# CONN.net
KiCad netlist of a schematic drawn in Altium Designer
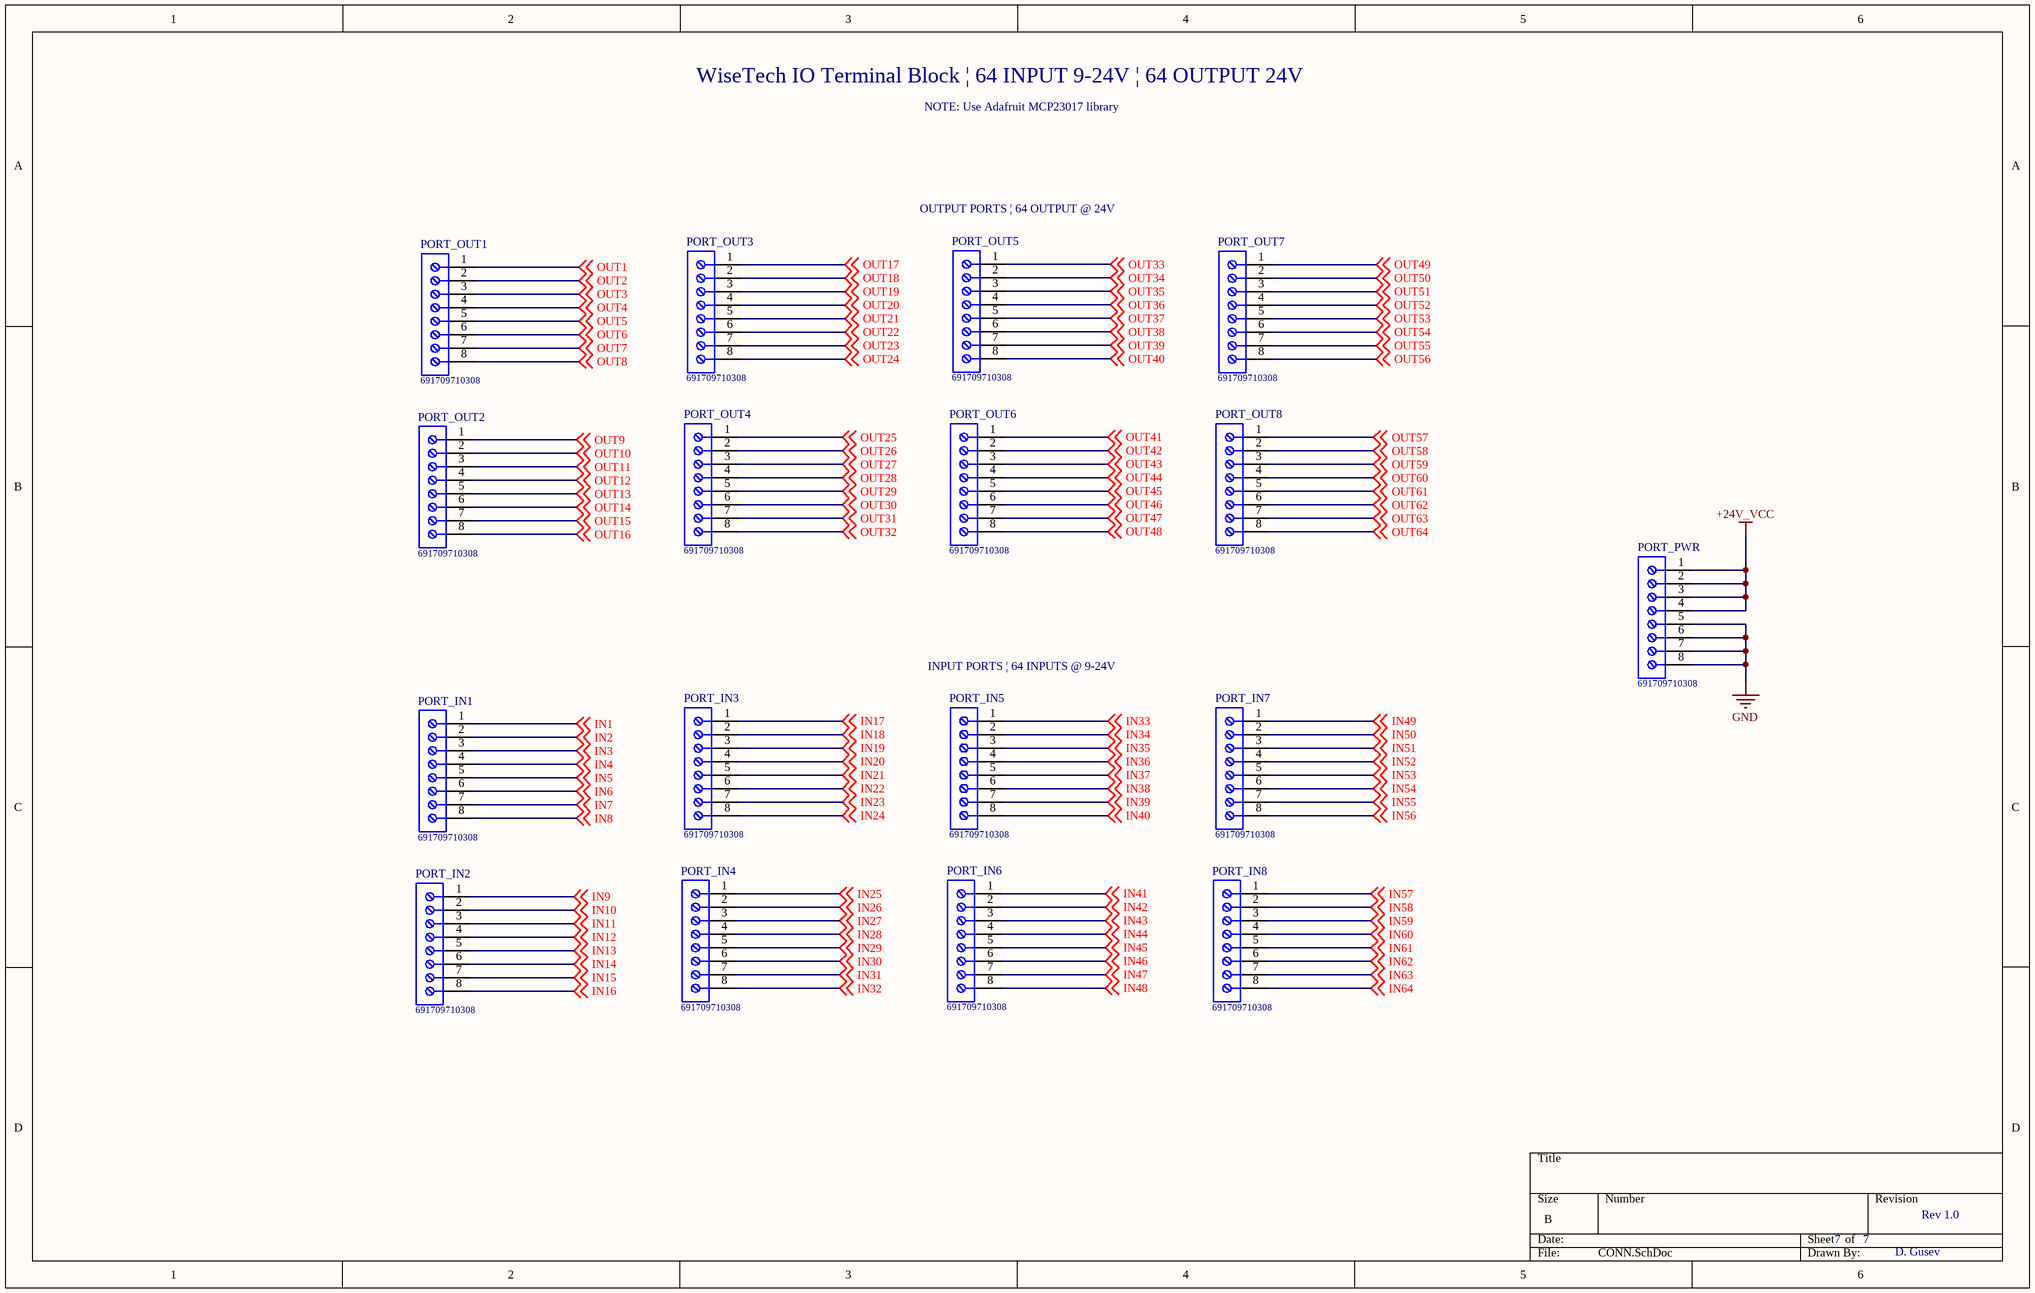
[diagram p0: CONN.SchDoc]

(export (version "E")
  (design (tool "Eeschema 10.0.6"))
  (components
    (comp (ref "PORT_IN1")
      (value "691709710308")
      (footprint "691709710308")
      (description "Serie 7097 - 5.00 mm Horizontal Entry SMT with Pressure Clamp WR-TBL, 8 pin")
      (fields (field (name "MANUFACTURER") "Wurth Elektronik") (field (name "PUBLISHER") "WurthElektronik"))
      (libsource (lib "") (part "WE-CN-1P-F-TB8_1"))
    )
    (comp (ref "PORT_IN2")
      (value "691709710308")
      (footprint "691709710308")
      (description "Serie 7097 - 5.00 mm Horizontal Entry SMT with Pressure Clamp WR-TBL, 8 pin")
      (fields (field (name "MANUFACTURER") "Wurth Elektronik") (field (name "PUBLISHER") "WurthElektronik"))
      (libsource (lib "") (part "WE-CN-1P-F-TB8_1"))
    )
    (comp (ref "PORT_IN3")
      (value "691709710308")
      (footprint "691709710308")
      (description "Serie 7097 - 5.00 mm Horizontal Entry SMT with Pressure Clamp WR-TBL, 8 pin")
      (fields (field (name "MANUFACTURER") "Wurth Elektronik") (field (name "PUBLISHER") "WurthElektronik"))
      (libsource (lib "") (part "WE-CN-1P-F-TB8_1"))
    )
    (comp (ref "PORT_IN4")
      (value "691709710308")
      (footprint "691709710308")
      (description "Serie 7097 - 5.00 mm Horizontal Entry SMT with Pressure Clamp WR-TBL, 8 pin")
      (fields (field (name "MANUFACTURER") "Wurth Elektronik") (field (name "PUBLISHER") "WurthElektronik"))
      (libsource (lib "") (part "WE-CN-1P-F-TB8_1"))
    )
    (comp (ref "PORT_IN5")
      (value "691709710308")
      (footprint "691709710308")
      (description "Serie 7097 - 5.00 mm Horizontal Entry SMT with Pressure Clamp WR-TBL, 8 pin")
      (fields (field (name "MANUFACTURER") "Wurth Elektronik") (field (name "PUBLISHER") "WurthElektronik"))
      (libsource (lib "") (part "WE-CN-1P-F-TB8_2"))
    )
    (comp (ref "PORT_IN6")
      (value "691709710308")
      (footprint "691709710308")
      (description "Serie 7097 - 5.00 mm Horizontal Entry SMT with Pressure Clamp WR-TBL, 8 pin")
      (fields (field (name "MANUFACTURER") "Wurth Elektronik") (field (name "PUBLISHER") "WurthElektronik"))
      (libsource (lib "") (part "WE-CN-1P-F-TB8_2"))
    )
    (comp (ref "PORT_IN7")
      (value "691709710308")
      (footprint "691709710308")
      (description "Serie 7097 - 5.00 mm Horizontal Entry SMT with Pressure Clamp WR-TBL, 8 pin")
      (fields (field (name "MANUFACTURER") "Wurth Elektronik") (field (name "PUBLISHER") "WurthElektronik"))
      (libsource (lib "") (part "WE-CN-1P-F-TB8_2"))
    )
    (comp (ref "PORT_IN8")
      (value "691709710308")
      (footprint "691709710308")
      (description "Serie 7097 - 5.00 mm Horizontal Entry SMT with Pressure Clamp WR-TBL, 8 pin")
      (fields (field (name "MANUFACTURER") "Wurth Elektronik") (field (name "PUBLISHER") "WurthElektronik"))
      (libsource (lib "") (part "WE-CN-1P-F-TB8_2"))
    )
    (comp (ref "PORT_OUT1")
      (value "691709710308")
      (footprint "691709710308")
      (description "Serie 7097 - 5.00 mm Horizontal Entry SMT with Pressure Clamp WR-TBL, 8 pin")
      (fields (field (name "MANUFACTURER") "Wurth Elektronik") (field (name "PUBLISHER") "WurthElektronik"))
      (libsource (lib "") (part "WE-CN-1P-F-TB8_4"))
    )
    (comp (ref "PORT_OUT2")
      (value "691709710308")
      (footprint "691709710308")
      (description "Serie 7097 - 5.00 mm Horizontal Entry SMT with Pressure Clamp WR-TBL, 8 pin")
      (fields (field (name "MANUFACTURER") "Wurth Elektronik") (field (name "PUBLISHER") "WurthElektronik"))
      (libsource (lib "") (part "WE-CN-1P-F-TB8_1"))
    )
    (comp (ref "PORT_OUT3")
      (value "691709710308")
      (footprint "691709710308")
      (description "Serie 7097 - 5.00 mm Horizontal Entry SMT with Pressure Clamp WR-TBL, 8 pin")
      (fields (field (name "MANUFACTURER") "Wurth Elektronik") (field (name "PUBLISHER") "WurthElektronik"))
      (libsource (lib "") (part "WE-CN-1P-F-TB8_4"))
    )
    (comp (ref "PORT_OUT4")
      (value "691709710308")
      (footprint "691709710308")
      (description "Serie 7097 - 5.00 mm Horizontal Entry SMT with Pressure Clamp WR-TBL, 8 pin")
      (fields (field (name "MANUFACTURER") "Wurth Elektronik") (field (name "PUBLISHER") "WurthElektronik"))
      (libsource (lib "") (part "WE-CN-1P-F-TB8_1"))
    )
    (comp (ref "PORT_OUT5")
      (value "691709710308")
      (footprint "691709710308")
      (description "Serie 7097 - 5.00 mm Horizontal Entry SMT with Pressure Clamp WR-TBL, 8 pin")
      (fields (field (name "MANUFACTURER") "Wurth Elektronik") (field (name "PUBLISHER") "WurthElektronik"))
      (libsource (lib "Altium Content Vault") (part "WE-CN-1P-F-TB8"))
    )
    (comp (ref "PORT_OUT6")
      (value "691709710308")
      (footprint "691709710308")
      (description "Serie 7097 - 5.00 mm Horizontal Entry SMT with Pressure Clamp WR-TBL, 8 pin")
      (fields (field (name "MANUFACTURER") "Wurth Elektronik") (field (name "PUBLISHER") "WurthElektronik"))
      (libsource (lib "") (part "WE-CN-1P-F-TB8_2"))
    )
    (comp (ref "PORT_OUT7")
      (value "691709710308")
      (footprint "691709710308")
      (description "Serie 7097 - 5.00 mm Horizontal Entry SMT with Pressure Clamp WR-TBL, 8 pin")
      (fields (field (name "MANUFACTURER") "Wurth Elektronik") (field (name "PUBLISHER") "WurthElektronik"))
      (libsource (lib "Altium Content Vault") (part "WE-CN-1P-F-TB8"))
    )
    (comp (ref "PORT_OUT8")
      (value "691709710308")
      (footprint "691709710308")
      (description "Serie 7097 - 5.00 mm Horizontal Entry SMT with Pressure Clamp WR-TBL, 8 pin")
      (fields (field (name "MANUFACTURER") "Wurth Elektronik") (field (name "PUBLISHER") "WurthElektronik"))
      (libsource (lib "") (part "WE-CN-1P-F-TB8_2"))
    )
    (comp (ref "PORT_PWR")
      (value "691709710308")
      (footprint "691709710308")
      (description "Serie 7097 - 5.00 mm Horizontal Entry SMT with Pressure Clamp WR-TBL, 8 pin")
      (fields (field (name "MANUFACTURER") "Wurth Elektronik") (field (name "PUBLISHER") "WurthElektronik"))
      (libsource (lib "") (part "WE-CN-1P-F-TB8_3"))
    )
  )
  (nets
    (net (code "1") (name "+24V_VCC") (class "Default")
      (node (ref "PORT_PWR") (pin "1") (pinfunction "1_1") (pintype "passive"))
      (node (ref "PORT_PWR") (pin "2") (pinfunction "2_2") (pintype "passive"))
      (node (ref "PORT_PWR") (pin "3") (pinfunction "3_3") (pintype "passive"))
      (node (ref "PORT_PWR") (pin "4") (pinfunction "4_4") (pintype "passive"))
    )
    (net (code "2") (name "GND") (class "Default")
      (node (ref "PORT_PWR") (pin "5") (pinfunction "5_5") (pintype "passive"))
      (node (ref "PORT_PWR") (pin "6") (pinfunction "6_6") (pintype "passive"))
      (node (ref "PORT_PWR") (pin "7") (pinfunction "7_7") (pintype "passive"))
      (node (ref "PORT_PWR") (pin "8") (pinfunction "8_8") (pintype "passive"))
    )
    (net (code "3") (name "IN1") (class "Default")
      (node (ref "PORT_IN1") (pin "1") (pinfunction "1_1") (pintype "passive"))
    )
    (net (code "4") (name "IN2") (class "Default")
      (node (ref "PORT_IN1") (pin "2") (pinfunction "2_2") (pintype "passive"))
    )
    (net (code "5") (name "IN3") (class "Default")
      (node (ref "PORT_IN1") (pin "3") (pinfunction "3_3") (pintype "passive"))
    )
    (net (code "6") (name "IN4") (class "Default")
      (node (ref "PORT_IN1") (pin "4") (pinfunction "4_4") (pintype "passive"))
    )
    (net (code "7") (name "IN5") (class "Default")
      (node (ref "PORT_IN1") (pin "5") (pinfunction "5_5") (pintype "passive"))
    )
    (net (code "8") (name "IN6") (class "Default")
      (node (ref "PORT_IN1") (pin "6") (pinfunction "6_6") (pintype "passive"))
    )
    (net (code "9") (name "IN7") (class "Default")
      (node (ref "PORT_IN1") (pin "7") (pinfunction "7_7") (pintype "passive"))
    )
    (net (code "10") (name "IN8") (class "Default")
      (node (ref "PORT_IN1") (pin "8") (pinfunction "8_8") (pintype "passive"))
    )
    (net (code "11") (name "IN9") (class "Default")
      (node (ref "PORT_IN2") (pin "1") (pinfunction "1_1") (pintype "passive"))
    )
    (net (code "12") (name "IN10") (class "Default")
      (node (ref "PORT_IN2") (pin "2") (pinfunction "2_2") (pintype "passive"))
    )
    (net (code "13") (name "IN11") (class "Default")
      (node (ref "PORT_IN2") (pin "3") (pinfunction "3_3") (pintype "passive"))
    )
    (net (code "14") (name "IN12") (class "Default")
      (node (ref "PORT_IN2") (pin "4") (pinfunction "4_4") (pintype "passive"))
    )
    (net (code "15") (name "IN13") (class "Default")
      (node (ref "PORT_IN2") (pin "5") (pinfunction "5_5") (pintype "passive"))
    )
    (net (code "16") (name "IN14") (class "Default")
      (node (ref "PORT_IN2") (pin "6") (pinfunction "6_6") (pintype "passive"))
    )
    (net (code "17") (name "IN15") (class "Default")
      (node (ref "PORT_IN2") (pin "7") (pinfunction "7_7") (pintype "passive"))
    )
    (net (code "18") (name "IN16") (class "Default")
      (node (ref "PORT_IN2") (pin "8") (pinfunction "8_8") (pintype "passive"))
    )
    (net (code "19") (name "IN17") (class "Default")
      (node (ref "PORT_IN3") (pin "1") (pinfunction "1_1") (pintype "passive"))
    )
    (net (code "20") (name "IN18") (class "Default")
      (node (ref "PORT_IN3") (pin "2") (pinfunction "2_2") (pintype "passive"))
    )
    (net (code "21") (name "IN19") (class "Default")
      (node (ref "PORT_IN3") (pin "3") (pinfunction "3_3") (pintype "passive"))
    )
    (net (code "22") (name "IN20") (class "Default")
      (node (ref "PORT_IN3") (pin "4") (pinfunction "4_4") (pintype "passive"))
    )
    (net (code "23") (name "IN21") (class "Default")
      (node (ref "PORT_IN3") (pin "5") (pinfunction "5_5") (pintype "passive"))
    )
    (net (code "24") (name "IN22") (class "Default")
      (node (ref "PORT_IN3") (pin "6") (pinfunction "6_6") (pintype "passive"))
    )
    (net (code "25") (name "IN23") (class "Default")
      (node (ref "PORT_IN3") (pin "7") (pinfunction "7_7") (pintype "passive"))
    )
    (net (code "26") (name "IN24") (class "Default")
      (node (ref "PORT_IN3") (pin "8") (pinfunction "8_8") (pintype "passive"))
    )
    (net (code "27") (name "IN25") (class "Default")
      (node (ref "PORT_IN4") (pin "1") (pinfunction "1_1") (pintype "passive"))
    )
    (net (code "28") (name "IN26") (class "Default")
      (node (ref "PORT_IN4") (pin "2") (pinfunction "2_2") (pintype "passive"))
    )
    (net (code "29") (name "IN27") (class "Default")
      (node (ref "PORT_IN4") (pin "3") (pinfunction "3_3") (pintype "passive"))
    )
    (net (code "30") (name "IN28") (class "Default")
      (node (ref "PORT_IN4") (pin "4") (pinfunction "4_4") (pintype "passive"))
    )
    (net (code "31") (name "IN29") (class "Default")
      (node (ref "PORT_IN4") (pin "5") (pinfunction "5_5") (pintype "passive"))
    )
    (net (code "32") (name "IN30") (class "Default")
      (node (ref "PORT_IN4") (pin "6") (pinfunction "6_6") (pintype "passive"))
    )
    (net (code "33") (name "IN31") (class "Default")
      (node (ref "PORT_IN4") (pin "7") (pinfunction "7_7") (pintype "passive"))
    )
    (net (code "34") (name "IN32") (class "Default")
      (node (ref "PORT_IN4") (pin "8") (pinfunction "8_8") (pintype "passive"))
    )
    (net (code "35") (name "IN33") (class "Default")
      (node (ref "PORT_IN5") (pin "1") (pinfunction "1_1") (pintype "passive"))
    )
    (net (code "36") (name "IN34") (class "Default")
      (node (ref "PORT_IN5") (pin "2") (pinfunction "2_2") (pintype "passive"))
    )
    (net (code "37") (name "IN35") (class "Default")
      (node (ref "PORT_IN5") (pin "3") (pinfunction "3_3") (pintype "passive"))
    )
    (net (code "38") (name "IN36") (class "Default")
      (node (ref "PORT_IN5") (pin "4") (pinfunction "4_4") (pintype "passive"))
    )
    (net (code "39") (name "IN37") (class "Default")
      (node (ref "PORT_IN5") (pin "5") (pinfunction "5_5") (pintype "passive"))
    )
    (net (code "40") (name "IN38") (class "Default")
      (node (ref "PORT_IN5") (pin "6") (pinfunction "6_6") (pintype "passive"))
    )
    (net (code "41") (name "IN39") (class "Default")
      (node (ref "PORT_IN5") (pin "7") (pinfunction "7_7") (pintype "passive"))
    )
    (net (code "42") (name "IN40") (class "Default")
      (node (ref "PORT_IN5") (pin "8") (pinfunction "8_8") (pintype "passive"))
    )
    (net (code "43") (name "IN41") (class "Default")
      (node (ref "PORT_IN6") (pin "1") (pinfunction "1_1") (pintype "passive"))
    )
    (net (code "44") (name "IN42") (class "Default")
      (node (ref "PORT_IN6") (pin "2") (pinfunction "2_2") (pintype "passive"))
    )
    (net (code "45") (name "IN43") (class "Default")
      (node (ref "PORT_IN6") (pin "3") (pinfunction "3_3") (pintype "passive"))
    )
    (net (code "46") (name "IN44") (class "Default")
      (node (ref "PORT_IN6") (pin "4") (pinfunction "4_4") (pintype "passive"))
    )
    (net (code "47") (name "IN45") (class "Default")
      (node (ref "PORT_IN6") (pin "5") (pinfunction "5_5") (pintype "passive"))
    )
    (net (code "48") (name "IN46") (class "Default")
      (node (ref "PORT_IN6") (pin "6") (pinfunction "6_6") (pintype "passive"))
    )
    (net (code "49") (name "IN47") (class "Default")
      (node (ref "PORT_IN6") (pin "7") (pinfunction "7_7") (pintype "passive"))
    )
    (net (code "50") (name "IN48") (class "Default")
      (node (ref "PORT_IN6") (pin "8") (pinfunction "8_8") (pintype "passive"))
    )
    (net (code "51") (name "IN49") (class "Default")
      (node (ref "PORT_IN7") (pin "1") (pinfunction "1_1") (pintype "passive"))
    )
    (net (code "52") (name "IN50") (class "Default")
      (node (ref "PORT_IN7") (pin "2") (pinfunction "2_2") (pintype "passive"))
    )
    (net (code "53") (name "IN51") (class "Default")
      (node (ref "PORT_IN7") (pin "3") (pinfunction "3_3") (pintype "passive"))
    )
    (net (code "54") (name "IN52") (class "Default")
      (node (ref "PORT_IN7") (pin "4") (pinfunction "4_4") (pintype "passive"))
    )
    (net (code "55") (name "IN53") (class "Default")
      (node (ref "PORT_IN7") (pin "5") (pinfunction "5_5") (pintype "passive"))
    )
    (net (code "56") (name "IN54") (class "Default")
      (node (ref "PORT_IN7") (pin "6") (pinfunction "6_6") (pintype "passive"))
    )
    (net (code "57") (name "IN55") (class "Default")
      (node (ref "PORT_IN7") (pin "7") (pinfunction "7_7") (pintype "passive"))
    )
    (net (code "58") (name "IN56") (class "Default")
      (node (ref "PORT_IN7") (pin "8") (pinfunction "8_8") (pintype "passive"))
    )
    (net (code "59") (name "IN57") (class "Default")
      (node (ref "PORT_IN8") (pin "1") (pinfunction "1_1") (pintype "passive"))
    )
    (net (code "60") (name "IN58") (class "Default")
      (node (ref "PORT_IN8") (pin "2") (pinfunction "2_2") (pintype "passive"))
    )
    (net (code "61") (name "IN59") (class "Default")
      (node (ref "PORT_IN8") (pin "3") (pinfunction "3_3") (pintype "passive"))
    )
    (net (code "62") (name "IN60") (class "Default")
      (node (ref "PORT_IN8") (pin "4") (pinfunction "4_4") (pintype "passive"))
    )
    (net (code "63") (name "IN61") (class "Default")
      (node (ref "PORT_IN8") (pin "5") (pinfunction "5_5") (pintype "passive"))
    )
    (net (code "64") (name "IN62") (class "Default")
      (node (ref "PORT_IN8") (pin "6") (pinfunction "6_6") (pintype "passive"))
    )
    (net (code "65") (name "IN63") (class "Default")
      (node (ref "PORT_IN8") (pin "7") (pinfunction "7_7") (pintype "passive"))
    )
    (net (code "66") (name "IN64") (class "Default")
      (node (ref "PORT_IN8") (pin "8") (pinfunction "8_8") (pintype "passive"))
    )
    (net (code "67") (name "OUT1") (class "Default")
      (node (ref "PORT_OUT1") (pin "1") (pinfunction "1_1") (pintype "passive"))
    )
    (net (code "68") (name "OUT2") (class "Default")
      (node (ref "PORT_OUT1") (pin "2") (pinfunction "2_2") (pintype "passive"))
    )
    (net (code "69") (name "OUT3") (class "Default")
      (node (ref "PORT_OUT1") (pin "3") (pinfunction "3_3") (pintype "passive"))
    )
    (net (code "70") (name "OUT4") (class "Default")
      (node (ref "PORT_OUT1") (pin "4") (pinfunction "4_4") (pintype "passive"))
    )
    (net (code "71") (name "OUT5") (class "Default")
      (node (ref "PORT_OUT1") (pin "5") (pinfunction "5_5") (pintype "passive"))
    )
    (net (code "72") (name "OUT6") (class "Default")
      (node (ref "PORT_OUT1") (pin "6") (pinfunction "6_6") (pintype "passive"))
    )
    (net (code "73") (name "OUT7") (class "Default")
      (node (ref "PORT_OUT1") (pin "7") (pinfunction "7_7") (pintype "passive"))
    )
    (net (code "74") (name "OUT8") (class "Default")
      (node (ref "PORT_OUT1") (pin "8") (pinfunction "8_8") (pintype "passive"))
    )
    (net (code "75") (name "OUT9") (class "Default")
      (node (ref "PORT_OUT2") (pin "1") (pinfunction "1_1") (pintype "passive"))
    )
    (net (code "76") (name "OUT10") (class "Default")
      (node (ref "PORT_OUT2") (pin "2") (pinfunction "2_2") (pintype "passive"))
    )
    (net (code "77") (name "OUT11") (class "Default")
      (node (ref "PORT_OUT2") (pin "3") (pinfunction "3_3") (pintype "passive"))
    )
    (net (code "78") (name "OUT12") (class "Default")
      (node (ref "PORT_OUT2") (pin "4") (pinfunction "4_4") (pintype "passive"))
    )
    (net (code "79") (name "OUT13") (class "Default")
      (node (ref "PORT_OUT2") (pin "5") (pinfunction "5_5") (pintype "passive"))
    )
    (net (code "80") (name "OUT14") (class "Default")
      (node (ref "PORT_OUT2") (pin "6") (pinfunction "6_6") (pintype "passive"))
    )
    (net (code "81") (name "OUT15") (class "Default")
      (node (ref "PORT_OUT2") (pin "7") (pinfunction "7_7") (pintype "passive"))
    )
    (net (code "82") (name "OUT16") (class "Default")
      (node (ref "PORT_OUT2") (pin "8") (pinfunction "8_8") (pintype "passive"))
    )
    (net (code "83") (name "OUT17") (class "Default")
      (node (ref "PORT_OUT3") (pin "1") (pinfunction "1_1") (pintype "passive"))
    )
    (net (code "84") (name "OUT18") (class "Default")
      (node (ref "PORT_OUT3") (pin "2") (pinfunction "2_2") (pintype "passive"))
    )
    (net (code "85") (name "OUT19") (class "Default")
      (node (ref "PORT_OUT3") (pin "3") (pinfunction "3_3") (pintype "passive"))
    )
    (net (code "86") (name "OUT20") (class "Default")
      (node (ref "PORT_OUT3") (pin "4") (pinfunction "4_4") (pintype "passive"))
    )
    (net (code "87") (name "OUT21") (class "Default")
      (node (ref "PORT_OUT3") (pin "5") (pinfunction "5_5") (pintype "passive"))
    )
    (net (code "88") (name "OUT22") (class "Default")
      (node (ref "PORT_OUT3") (pin "6") (pinfunction "6_6") (pintype "passive"))
    )
    (net (code "89") (name "OUT23") (class "Default")
      (node (ref "PORT_OUT3") (pin "7") (pinfunction "7_7") (pintype "passive"))
    )
    (net (code "90") (name "OUT24") (class "Default")
      (node (ref "PORT_OUT3") (pin "8") (pinfunction "8_8") (pintype "passive"))
    )
    (net (code "91") (name "OUT25") (class "Default")
      (node (ref "PORT_OUT4") (pin "1") (pinfunction "1_1") (pintype "passive"))
    )
    (net (code "92") (name "OUT26") (class "Default")
      (node (ref "PORT_OUT4") (pin "2") (pinfunction "2_2") (pintype "passive"))
    )
    (net (code "93") (name "OUT27") (class "Default")
      (node (ref "PORT_OUT4") (pin "3") (pinfunction "3_3") (pintype "passive"))
    )
    (net (code "94") (name "OUT28") (class "Default")
      (node (ref "PORT_OUT4") (pin "4") (pinfunction "4_4") (pintype "passive"))
    )
    (net (code "95") (name "OUT29") (class "Default")
      (node (ref "PORT_OUT4") (pin "5") (pinfunction "5_5") (pintype "passive"))
    )
    (net (code "96") (name "OUT30") (class "Default")
      (node (ref "PORT_OUT4") (pin "6") (pinfunction "6_6") (pintype "passive"))
    )
    (net (code "97") (name "OUT31") (class "Default")
      (node (ref "PORT_OUT4") (pin "7") (pinfunction "7_7") (pintype "passive"))
    )
    (net (code "98") (name "OUT32") (class "Default")
      (node (ref "PORT_OUT4") (pin "8") (pinfunction "8_8") (pintype "passive"))
    )
    (net (code "99") (name "OUT33") (class "Default")
      (node (ref "PORT_OUT5") (pin "1") (pinfunction "1_1") (pintype "passive"))
    )
    (net (code "100") (name "OUT34") (class "Default")
      (node (ref "PORT_OUT5") (pin "2") (pinfunction "2_2") (pintype "passive"))
    )
    (net (code "101") (name "OUT35") (class "Default")
      (node (ref "PORT_OUT5") (pin "3") (pinfunction "3_3") (pintype "passive"))
    )
    (net (code "102") (name "OUT36") (class "Default")
      (node (ref "PORT_OUT5") (pin "4") (pinfunction "4_4") (pintype "passive"))
    )
    (net (code "103") (name "OUT37") (class "Default")
      (node (ref "PORT_OUT5") (pin "5") (pinfunction "5_5") (pintype "passive"))
    )
    (net (code "104") (name "OUT38") (class "Default")
      (node (ref "PORT_OUT5") (pin "6") (pinfunction "6_6") (pintype "passive"))
    )
    (net (code "105") (name "OUT39") (class "Default")
      (node (ref "PORT_OUT5") (pin "7") (pinfunction "7_7") (pintype "passive"))
    )
    (net (code "106") (name "OUT40") (class "Default")
      (node (ref "PORT_OUT5") (pin "8") (pinfunction "8_8") (pintype "passive"))
    )
    (net (code "107") (name "OUT41") (class "Default")
      (node (ref "PORT_OUT6") (pin "1") (pinfunction "1_1") (pintype "passive"))
    )
    (net (code "108") (name "OUT42") (class "Default")
      (node (ref "PORT_OUT6") (pin "2") (pinfunction "2_2") (pintype "passive"))
    )
    (net (code "109") (name "OUT43") (class "Default")
      (node (ref "PORT_OUT6") (pin "3") (pinfunction "3_3") (pintype "passive"))
    )
    (net (code "110") (name "OUT44") (class "Default")
      (node (ref "PORT_OUT6") (pin "4") (pinfunction "4_4") (pintype "passive"))
    )
    (net (code "111") (name "OUT45") (class "Default")
      (node (ref "PORT_OUT6") (pin "5") (pinfunction "5_5") (pintype "passive"))
    )
    (net (code "112") (name "OUT46") (class "Default")
      (node (ref "PORT_OUT6") (pin "6") (pinfunction "6_6") (pintype "passive"))
    )
    (net (code "113") (name "OUT47") (class "Default")
      (node (ref "PORT_OUT6") (pin "7") (pinfunction "7_7") (pintype "passive"))
    )
    (net (code "114") (name "OUT48") (class "Default")
      (node (ref "PORT_OUT6") (pin "8") (pinfunction "8_8") (pintype "passive"))
    )
    (net (code "115") (name "OUT49") (class "Default")
      (node (ref "PORT_OUT7") (pin "1") (pinfunction "1_1") (pintype "passive"))
    )
    (net (code "116") (name "OUT50") (class "Default")
      (node (ref "PORT_OUT7") (pin "2") (pinfunction "2_2") (pintype "passive"))
    )
    (net (code "117") (name "OUT51") (class "Default")
      (node (ref "PORT_OUT7") (pin "3") (pinfunction "3_3") (pintype "passive"))
    )
    (net (code "118") (name "OUT52") (class "Default")
      (node (ref "PORT_OUT7") (pin "4") (pinfunction "4_4") (pintype "passive"))
    )
    (net (code "119") (name "OUT53") (class "Default")
      (node (ref "PORT_OUT7") (pin "5") (pinfunction "5_5") (pintype "passive"))
    )
    (net (code "120") (name "OUT54") (class "Default")
      (node (ref "PORT_OUT7") (pin "6") (pinfunction "6_6") (pintype "passive"))
    )
    (net (code "121") (name "OUT55") (class "Default")
      (node (ref "PORT_OUT7") (pin "7") (pinfunction "7_7") (pintype "passive"))
    )
    (net (code "122") (name "OUT56") (class "Default")
      (node (ref "PORT_OUT7") (pin "8") (pinfunction "8_8") (pintype "passive"))
    )
    (net (code "123") (name "OUT57") (class "Default")
      (node (ref "PORT_OUT8") (pin "1") (pinfunction "1_1") (pintype "passive"))
    )
    (net (code "124") (name "OUT58") (class "Default")
      (node (ref "PORT_OUT8") (pin "2") (pinfunction "2_2") (pintype "passive"))
    )
    (net (code "125") (name "OUT59") (class "Default")
      (node (ref "PORT_OUT8") (pin "3") (pinfunction "3_3") (pintype "passive"))
    )
    (net (code "126") (name "OUT60") (class "Default")
      (node (ref "PORT_OUT8") (pin "4") (pinfunction "4_4") (pintype "passive"))
    )
    (net (code "127") (name "OUT61") (class "Default")
      (node (ref "PORT_OUT8") (pin "5") (pinfunction "5_5") (pintype "passive"))
    )
    (net (code "128") (name "OUT62") (class "Default")
      (node (ref "PORT_OUT8") (pin "6") (pinfunction "6_6") (pintype "passive"))
    )
    (net (code "129") (name "OUT63") (class "Default")
      (node (ref "PORT_OUT8") (pin "7") (pinfunction "7_7") (pintype "passive"))
    )
    (net (code "130") (name "OUT64") (class "Default")
      (node (ref "PORT_OUT8") (pin "8") (pinfunction "8_8") (pintype "passive"))
    )
  )
)
